# n2k-breakout-4_0-ISO.net
KiCad netlist of a schematic drawn in EAGLE
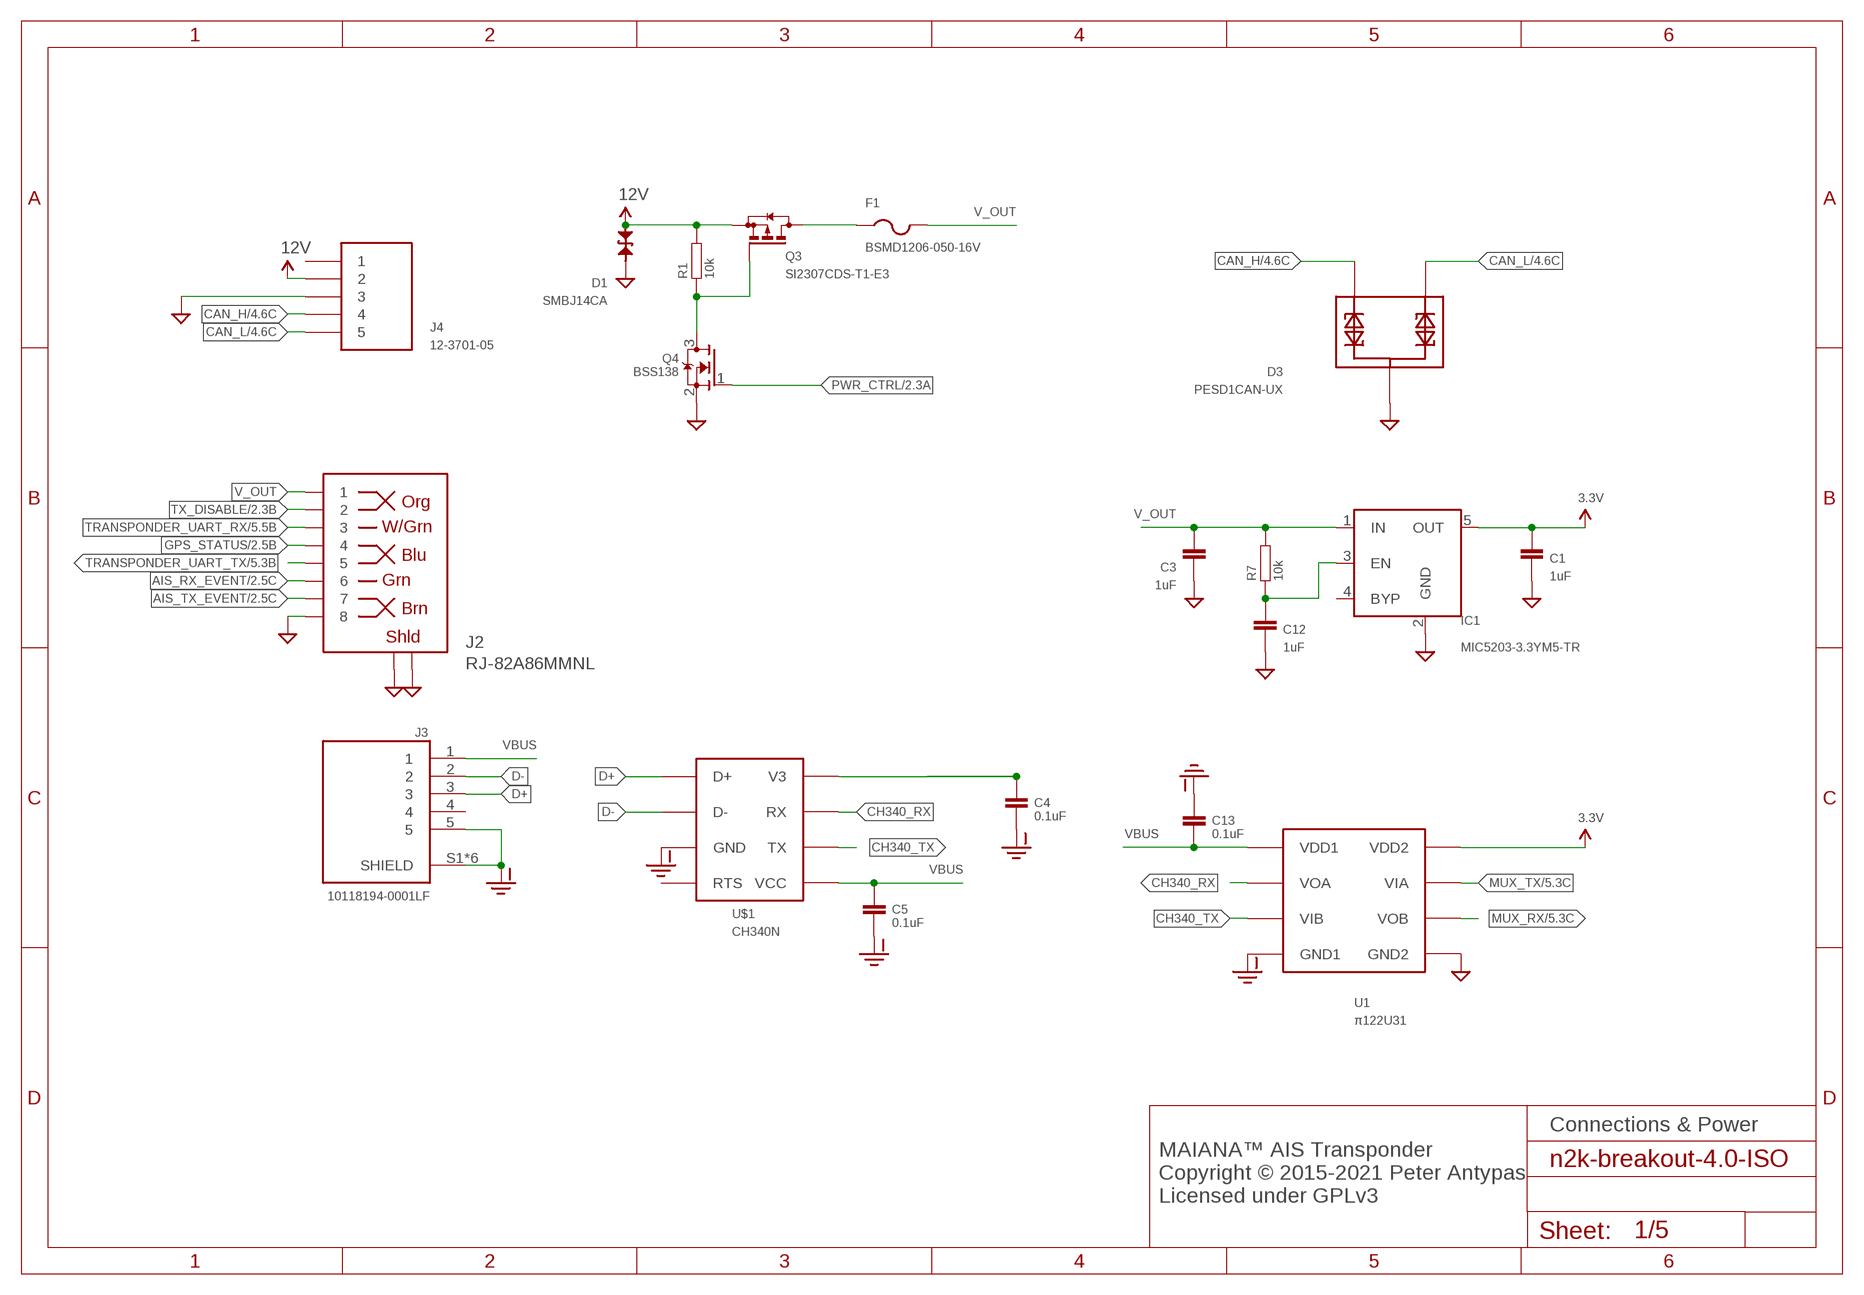
[diagram p0: schematic, sheet 1]
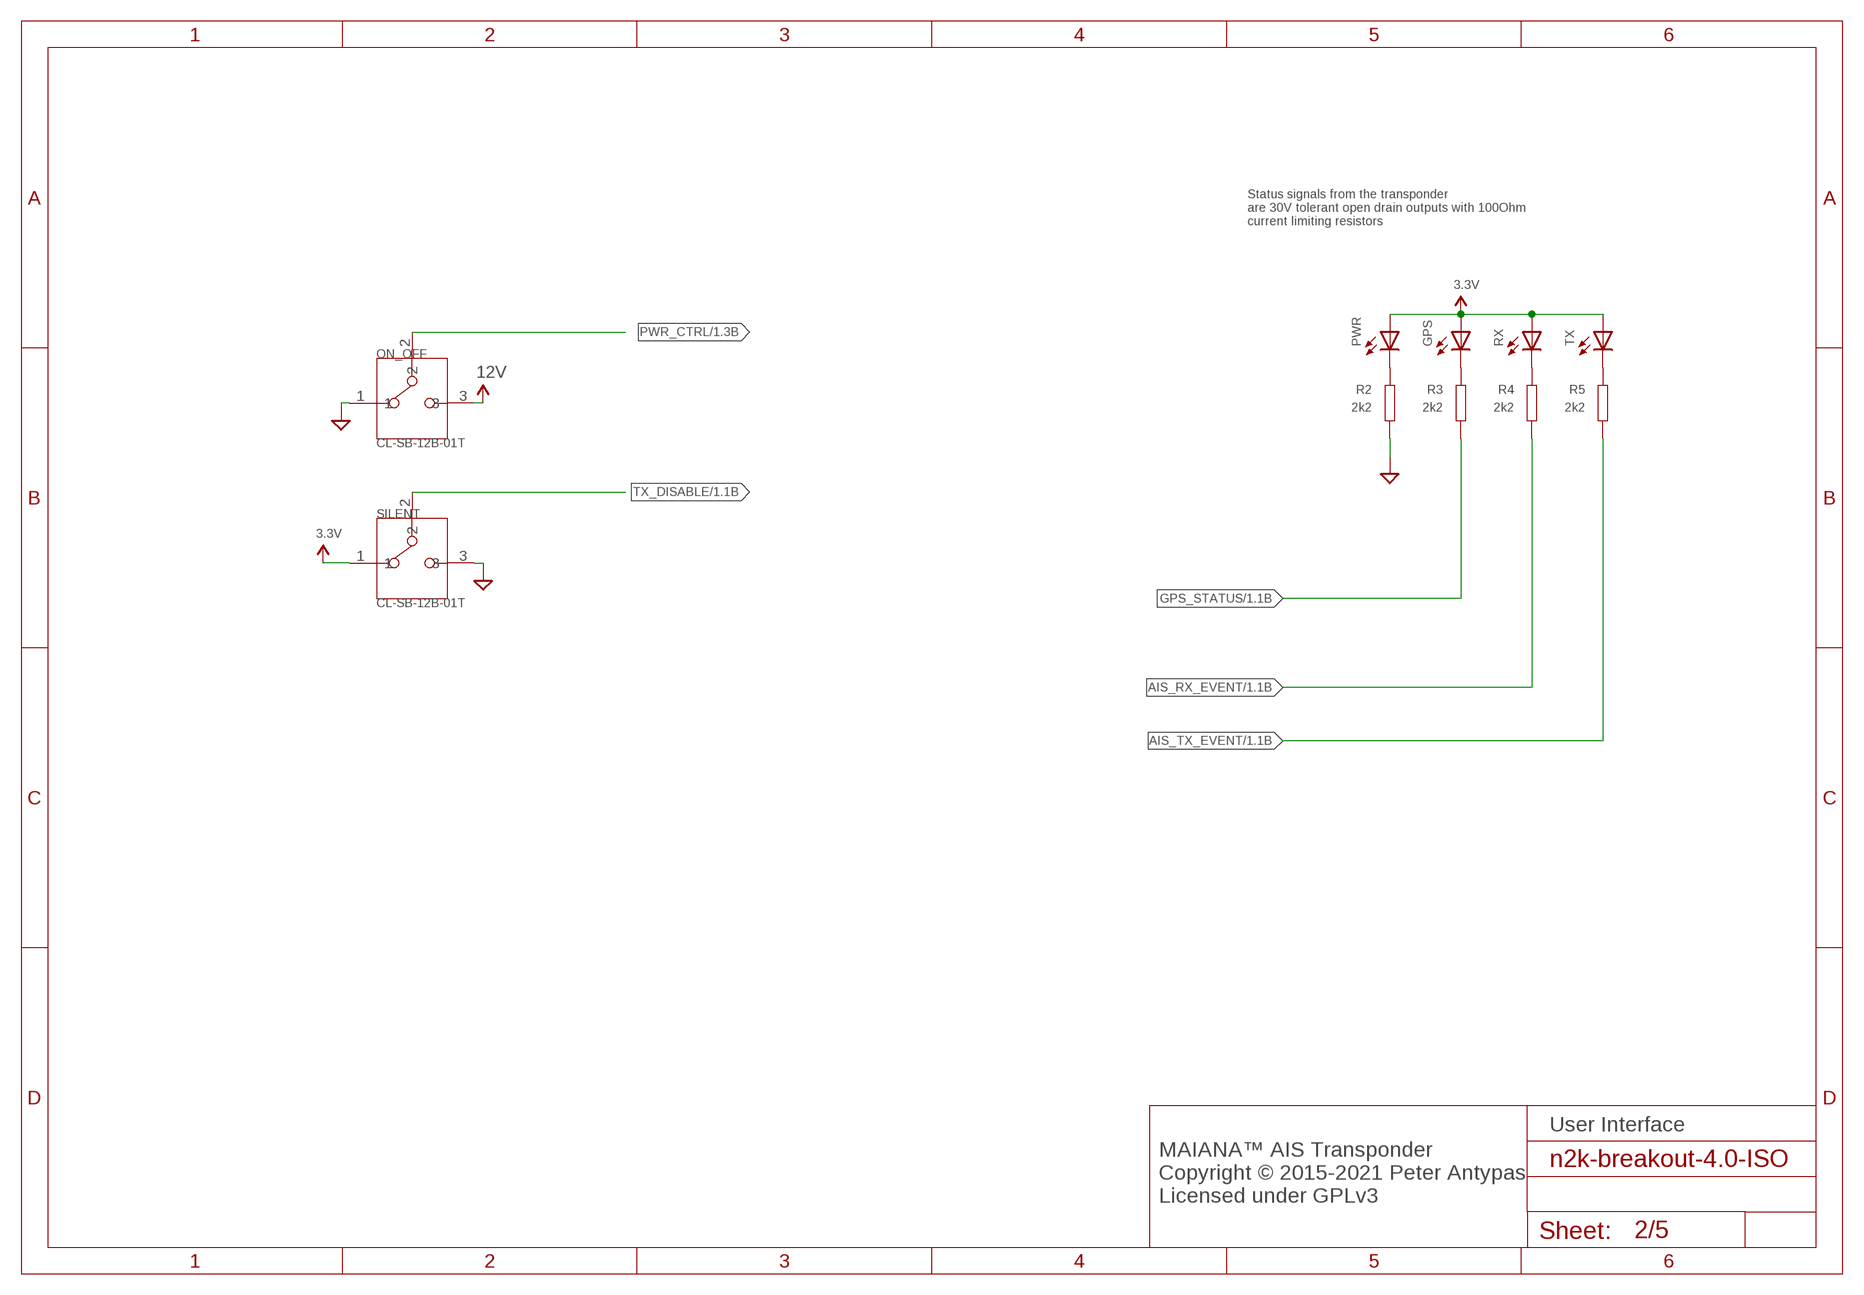
[diagram p1: schematic, sheet 2]
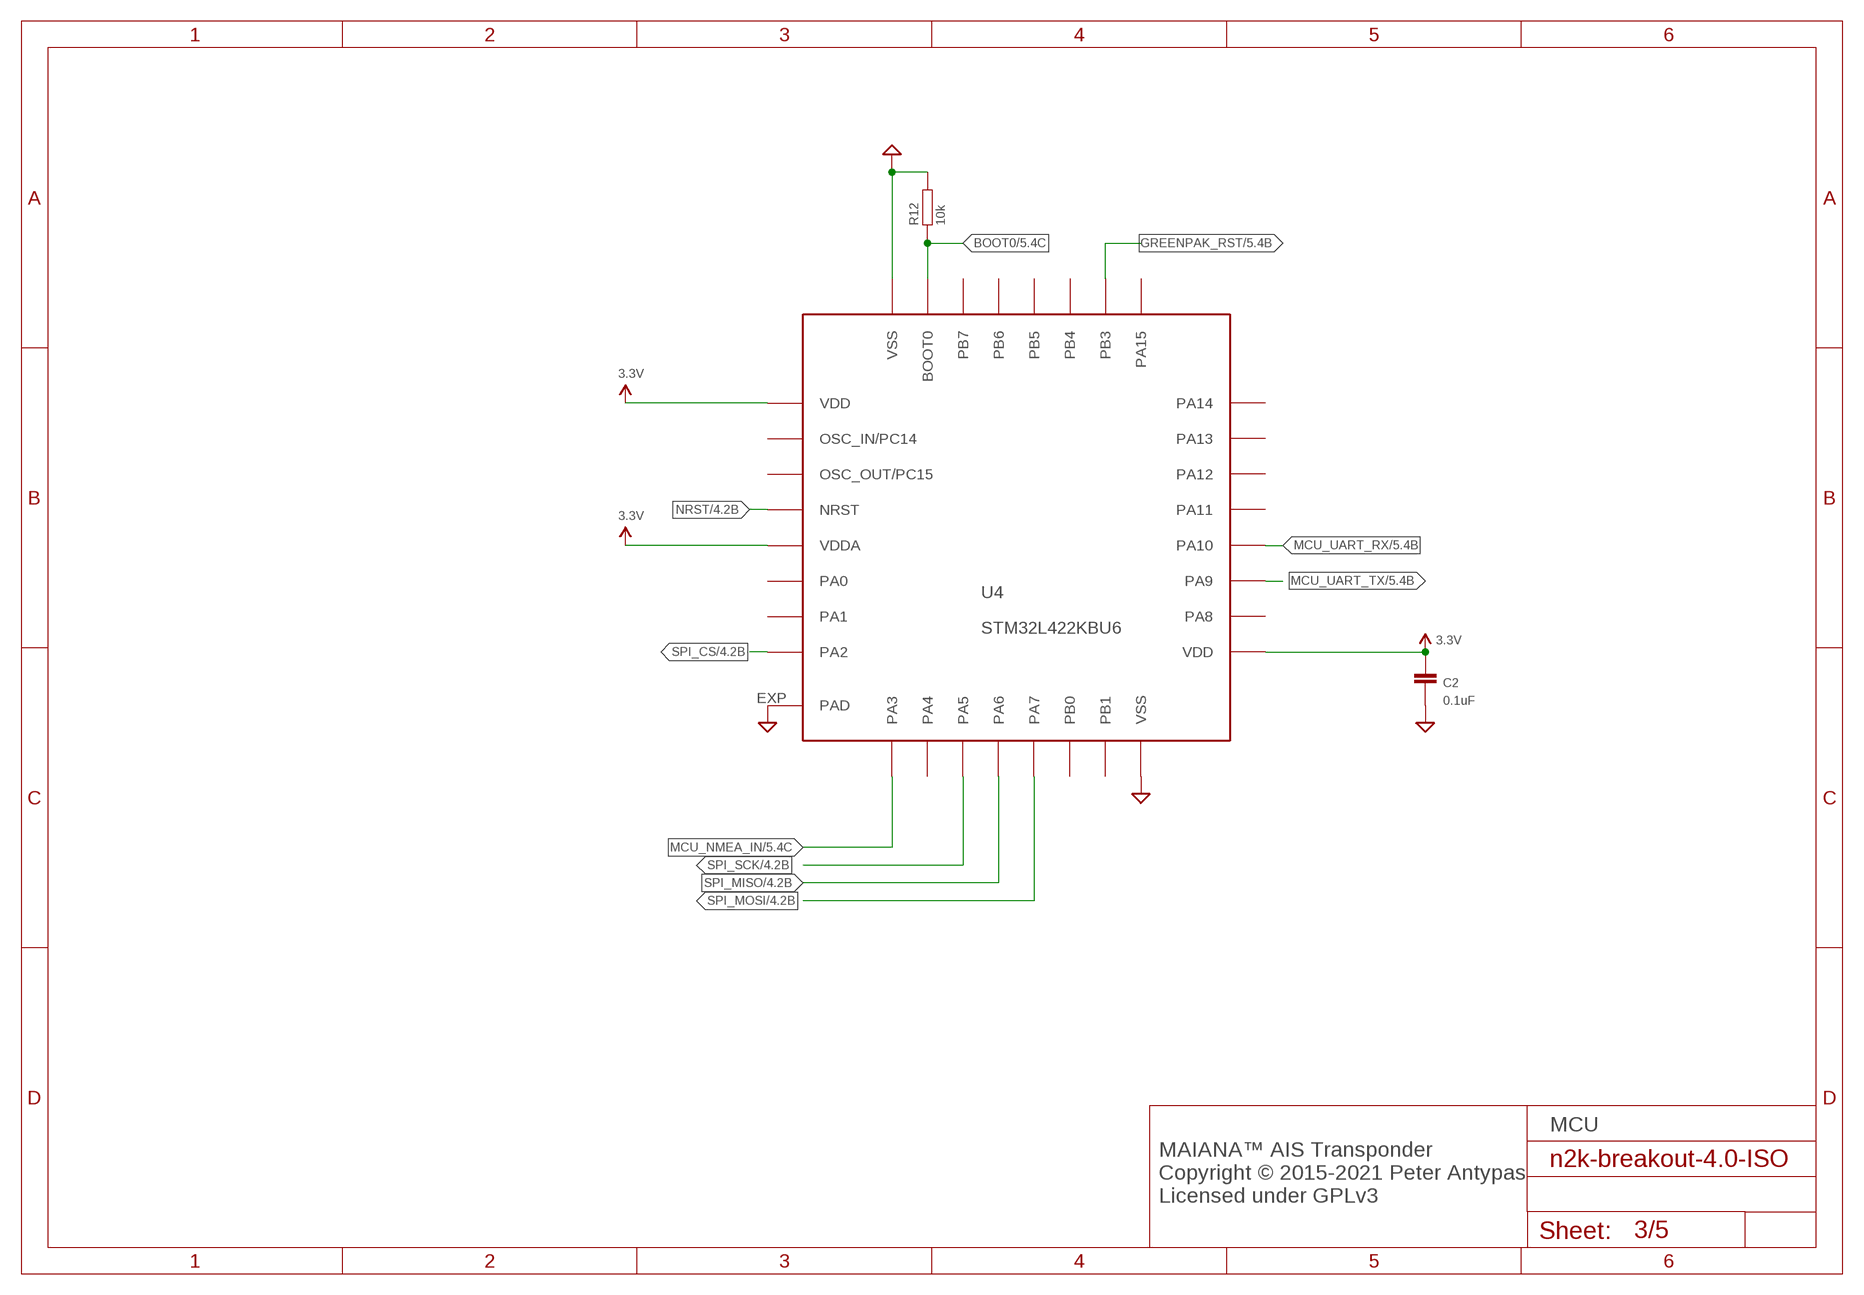
[diagram p2: schematic, sheet 3]
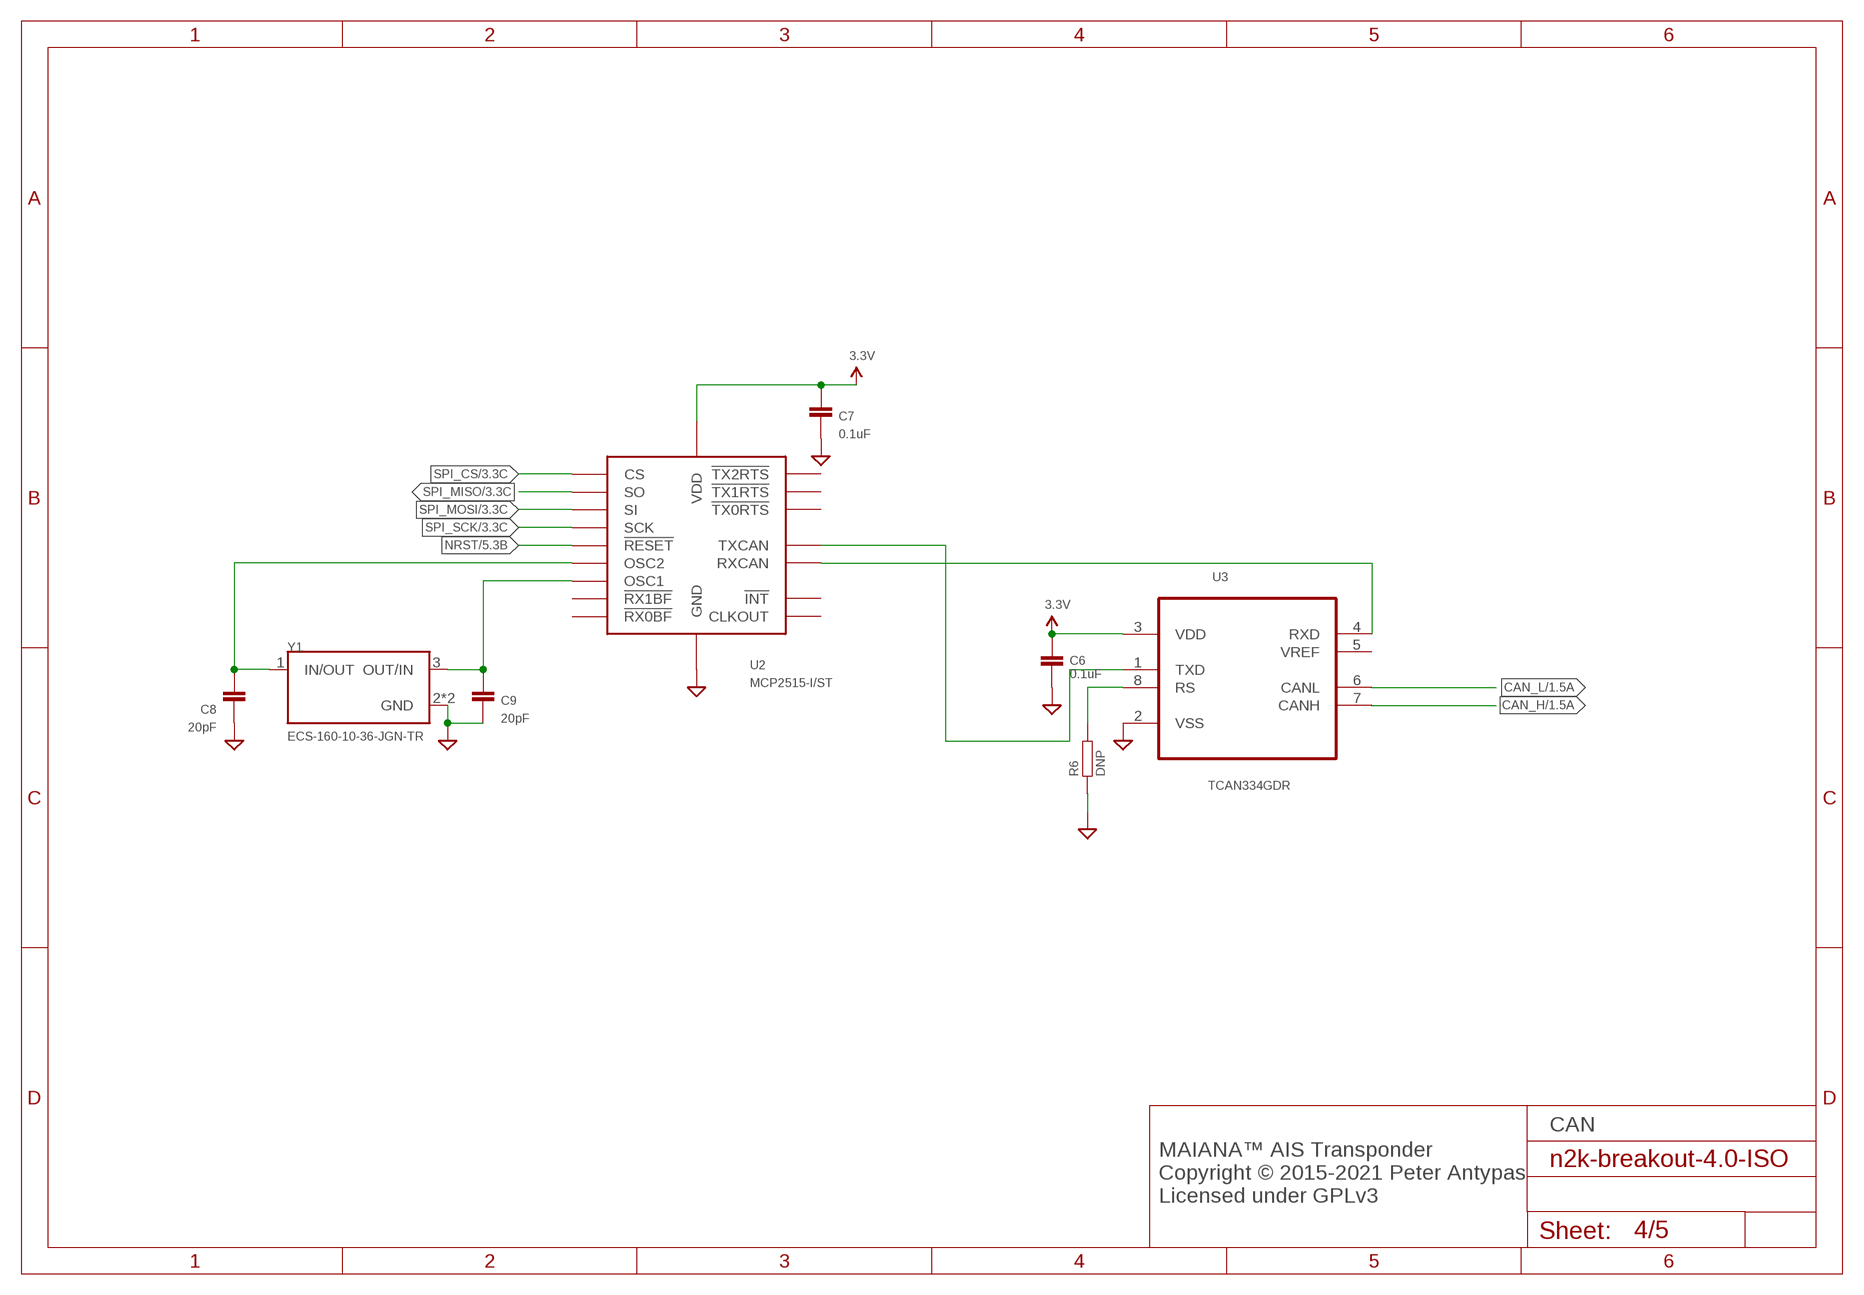
[diagram p3: schematic, sheet 4]
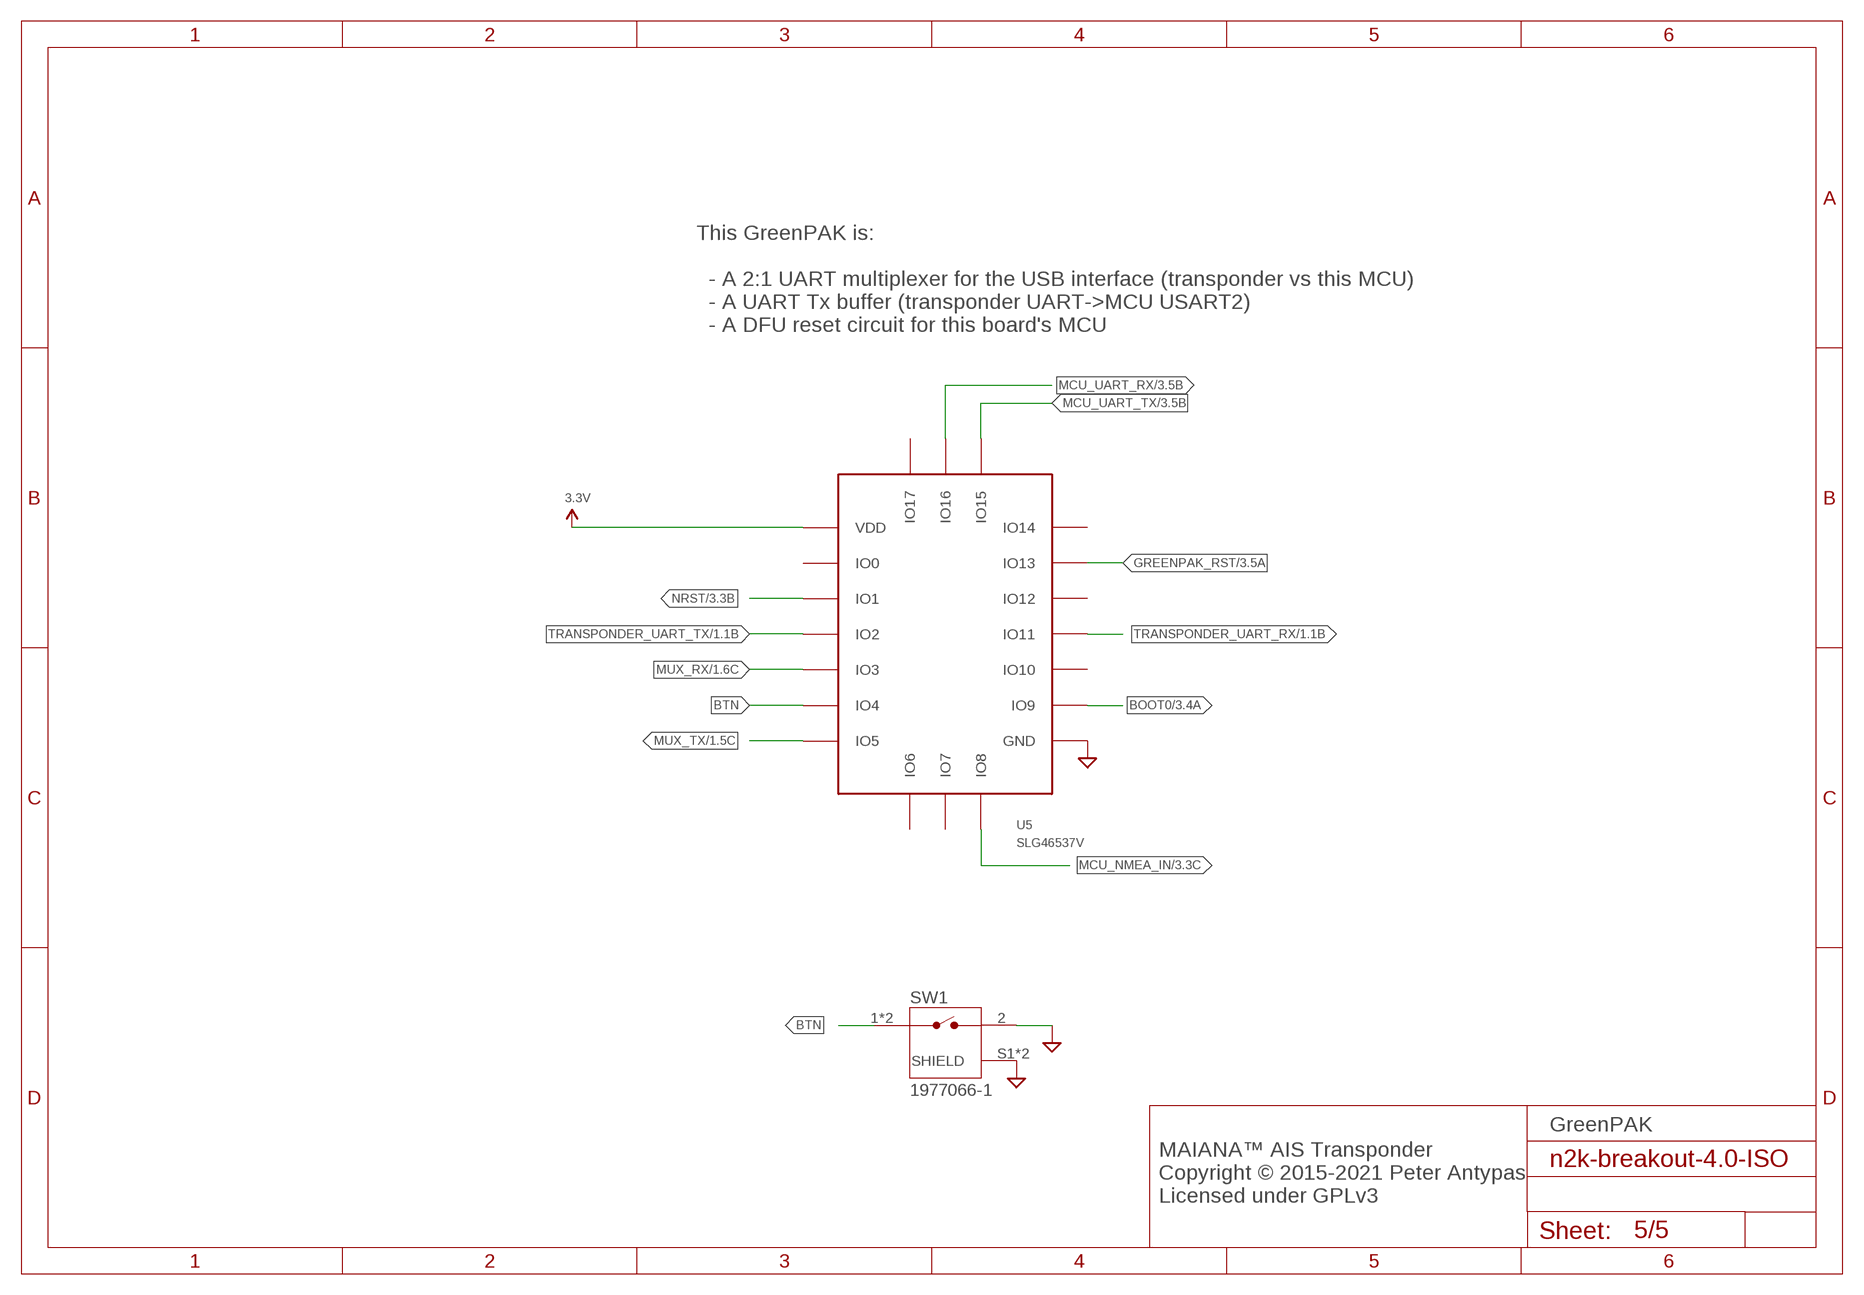
[diagram p4: schematic, sheet 5]

(export (version "E")
  (design (tool "Eeschema 10.0.6"))
  (components
    (comp (ref "GPS")
      (value "LEDCHIPLED_1206")
      (footprint "eagle-import:CHIPLED_1206")
      (fields (field (name "PARTNO") "TJ-S3216CL9T5ALC2G-A5"))
      (libsource (lib "eagle-import") (part "LEDCHIPLED_1206"))
    )
    (comp (ref "ON_OFF")
      (value "CL-SB-12B-01T")
      (footprint "eagle-import:CL-SB-12B")
      (fields (field (name "MF") "Nidec Copal"))
      (libsource (lib "eagle-import") (part "CL-SB-12B-01T"))
    )
    (comp (ref "PWR")
      (value "LEDCHIPLED_1206")
      (footprint "eagle-import:CHIPLED_1206")
      (fields (field (name "PARTNO") "TJ-S3216CL9T5ALC2G-A5"))
      (libsource (lib "eagle-import") (part "LEDCHIPLED_1206"))
    )
    (comp (ref "R2")
      (value "2k2")
      (footprint "eagle-import:0603")
      (fields (field (name "PARTNO") "CR0603-FX-2201ELF "))
      (libsource (lib "eagle-import") (part "RESISTOR0603"))
    )
    (comp (ref "R3")
      (value "2k2")
      (footprint "eagle-import:0603")
      (fields (field (name "PARTNO") "CR0603-FX-2201ELF"))
      (libsource (lib "eagle-import") (part "RESISTOR0603"))
    )
    (comp (ref "R4")
      (value "2k2")
      (footprint "eagle-import:0603")
      (fields (field (name "PARTNO") "CR0603-FX-2201ELF "))
      (libsource (lib "eagle-import") (part "RESISTOR0603"))
    )
    (comp (ref "R5")
      (value "2k2")
      (footprint "eagle-import:0603")
      (fields (field (name "PARTNO") "CR0603-FX-2201ELF "))
      (libsource (lib "eagle-import") (part "RESISTOR0603"))
    )
    (comp (ref "RX")
      (value "LEDCHIPLED_1206")
      (footprint "eagle-import:CHIPLED_1206")
      (fields (field (name "PARTNO") "TJ-S3216CL9T5ALC2G-A5"))
      (libsource (lib "eagle-import") (part "LEDCHIPLED_1206"))
    )
    (comp (ref "SILENT")
      (value "CL-SB-12B-01T")
      (footprint "eagle-import:CL-SB-12B")
      (fields (field (name "MF") "Nidec Copal"))
      (libsource (lib "eagle-import") (part "CL-SB-12B-01T"))
    )
    (comp (ref "TX")
      (value "LEDCHIPLED_1206")
      (footprint "eagle-import:CHIPLED_1206")
      (fields (field (name "PARTNO") "TJ-S3216CL9T5ALC2G-A5"))
      (libsource (lib "eagle-import") (part "LEDCHIPLED_1206"))
    )
    (comp (ref "C1")
      (value "1uF")
      (footprint "eagle-import:0603")
      (fields (field (name "PARTNO") "CC0603KRX5R8BB105 "))
      (libsource (lib "eagle-import") (part "CAPACITOR0603"))
    )
    (comp (ref "C3")
      (value "1uF")
      (footprint "eagle-import:0603")
      (fields (field (name "PARTNO") "CC0603KRX5R8BB105 "))
      (libsource (lib "eagle-import") (part "CAPACITOR0603"))
    )
    (comp (ref "C4")
      (value "0.1uF")
      (footprint "eagle-import:0603")
      (fields (field (name "PARTNO") "06035C104KAT2A "))
      (libsource (lib "eagle-import") (part "CAPACITOR0603"))
    )
    (comp (ref "C5")
      (value "0.1uF")
      (footprint "eagle-import:0603")
      (fields (field (name "PARTNO") "06035C104KAT2A "))
      (libsource (lib "eagle-import") (part "CAPACITOR0603"))
    )
    (comp (ref "C12")
      (value "1uF")
      (footprint "eagle-import:0603")
      (fields (field (name "PARTNO") "CC0603KRX5R8BB105 "))
      (libsource (lib "eagle-import") (part "CAPACITOR0603"))
    )
    (comp (ref "C13")
      (value "0.1uF")
      (footprint "eagle-import:0603")
      (fields (field (name "PARTNO") "06035C104KAT2A "))
      (libsource (lib "eagle-import") (part "CAPACITOR0603"))
    )
    (comp (ref "D1")
      (value "SMBJ14CA")
      (footprint "eagle-import:SMB-BIDIR")
      (fields (field (name "PARTNO") "SMBJ14CA "))
      (libsource (lib "eagle-import") (part "DIODE-TVS-BIDIRSMB"))
    )
    (comp (ref "D3")
      (value "PESD1CAN-UX")
      (footprint "eagle-import:SOT65P210X110-3N")
      (libsource (lib "eagle-import") (part "PESD1CAN-UX"))
    )
    (comp (ref "F1")
      (value "BSMD1206-050-16V")
      (footprint "eagle-import:R1206")
      (fields (field (name "PARTNO") "BSMD1206-050-16V "))
      (libsource (lib "eagle-import") (part "PTCFUSE-1206"))
    )
    (comp (ref "IC1")
      (value "MIC5203-3.3YM5-TR")
      (footprint "eagle-import:SOT23-5")
      (libsource (lib "eagle-import") (part "MIC5219XX"))
    )
    (comp (ref "J2")
      (value "RJ-82A86MMNL")
      (footprint "eagle-import:RJ-82A86MMNL")
      (libsource (lib "eagle-import") (part "RJ-82A86MMNL"))
    )
    (comp (ref "J3")
      (value "10118194-0001LF")
      (footprint "eagle-import:AMPHENOL_10118194-0001LF")
      (fields (field (name "MF") "Amphenol ICC (FCI)"))
      (libsource (lib "eagle-import") (part "10118194-0001LF"))
    )
    (comp (ref "J4")
      (value "12-3701-05")
      (footprint "eagle-import:MICRO_C_5PIN")
      (libsource (lib "eagle-import") (part "12-3701-05"))
    )
    (comp (ref "Q3")
      (value "SI2307CDS-T1-E3")
      (footprint "eagle-import:SOT23")
      (fields (field (name "PARTNO") "SI2307CDS-T1-E3 "))
      (libsource (lib "eagle-import") (part "BSS84"))
    )
    (comp (ref "Q4")
      (value "BSS138")
      (footprint "eagle-import:SOT23")
      (libsource (lib "eagle-import") (part "MOSFET-NREFLOW"))
    )
    (comp (ref "R1")
      (value "10k")
      (footprint "eagle-import:0603")
      (fields (field (name "PARTNO") "RC0603FR-0710KL"))
      (libsource (lib "eagle-import") (part "RESISTOR0603"))
    )
    (comp (ref "R7")
      (value "10k")
      (footprint "eagle-import:0603")
      (fields (field (name "PARTNO") "RC0603FR-0710KL"))
      (libsource (lib "eagle-import") (part "RESISTOR0603"))
    )
    (comp (ref "U$1")
      (value "CH340N")
      (footprint "eagle-import:SOIC-8")
      (libsource (lib "eagle-import") (part "CH330N"))
    )
    (comp (ref "U1")
      (value "π122U31")
      (footprint "eagle-import:SOIC8")
      (libsource (lib "eagle-import") (part "PI122U3X"))
    )
    (comp (ref "C6")
      (value "0.1uF")
      (footprint "eagle-import:0603")
      (fields (field (name "PARTNO") "06035C104KAT2A "))
      (libsource (lib "eagle-import") (part "CAPACITOR0603"))
    )
    (comp (ref "C7")
      (value "0.1uF")
      (footprint "eagle-import:0603")
      (fields (field (name "PARTNO") "06035C104KAT2A "))
      (libsource (lib "eagle-import") (part "CAPACITOR0603"))
    )
    (comp (ref "C8")
      (value "20pF")
      (footprint "eagle-import:0603")
      (fields (field (name "PARTNO") "GRM1885C1H200JA01D "))
      (libsource (lib "eagle-import") (part "CAPACITOR0603"))
    )
    (comp (ref "C9")
      (value "20pF")
      (footprint "eagle-import:0603")
      (fields (field (name "PARTNO") "GRM1885C1H200JA01D "))
      (libsource (lib "eagle-import") (part "CAPACITOR0603"))
    )
    (comp (ref "R6")
      (value "DNP")
      (footprint "eagle-import:0603")
      (fields (field (name "PARTNO") "RC0603FR-0710KL"))
      (libsource (lib "eagle-import") (part "RESISTOR0603"))
    )
    (comp (ref "U2")
      (value "MCP2515-I/ST")
      (footprint "eagle-import:TSSOP20")
      (libsource (lib "eagle-import") (part "MCP2515TSSOP20"))
    )
    (comp (ref "U3")
      (value "TCAN334GDR")
      (footprint "eagle-import:SOIC127P600X175-8N")
      (fields (field (name "MF") "Microchip") (field (name "MP") "MCP2551T-I/SN"))
      (libsource (lib "eagle-import") (part "MCP2551T-I/SN"))
    )
    (comp (ref "Y1")
      (value "ECS-160-10-36-JGN-TR")
      (footprint "eagle-import:XTAL_ECS-160-10-36-JGN-TR")
      (fields (field (name "MF") "ECS Inc.") (field (name "MP") "ECS-300-8-36CKM-TR"))
      (libsource (lib "eagle-import") (part "ECS-300-8-36CKM-TR"))
    )
    (comp (ref "SW1")
      (value "1977066-1")
      (footprint "eagle-import:TE_1977066-1")
      (fields (field (name "MF") "TE Connectivity"))
      (libsource (lib "eagle-import") (part "1977066-1"))
    )
    (comp (ref "U5")
      (value "SLG46537V")
      (footprint "eagle-import:STQFN20L")
      (libsource (lib "eagle-import") (part "SLG46537"))
    )
    (comp (ref "C2")
      (value "0.1uF")
      (footprint "eagle-import:0603")
      (fields (field (name "PARTNO") "06035C104KAT2A "))
      (libsource (lib "eagle-import") (part "CAPACITOR0603"))
    )
    (comp (ref "R12")
      (value "10k")
      (footprint "eagle-import:0603")
      (fields (field (name "PARTNO") "RC0603FR-0710KL"))
      (libsource (lib "eagle-import") (part "RESISTOR0603"))
    )
    (comp (ref "U4")
      (value "STM32L422KBU6")
      (footprint "eagle-import:QFN32")
      (libsource (lib "eagle-import") (part "STM32L432KXXX"))
    )
  )
  (nets
    (net (code "1") (name "3.3V") (class "Default")
      (node (ref "C1") (pin "P$1") (pinfunction "1_P$1") (pintype "passive"))
      (node (ref "C2") (pin "P$1") (pinfunction "1_P$1") (pintype "passive"))
      (node (ref "C6") (pin "P$1") (pinfunction "1_P$1") (pintype "passive"))
      (node (ref "C7") (pin "P$1") (pinfunction "1_P$1") (pintype "passive"))
      (node (ref "GPS") (pin "A") (pinfunction "A_A") (pintype "passive"))
      (node (ref "IC1") (pin "5") (pinfunction "OUT_5") (pintype "output"))
      (node (ref "PWR") (pin "A") (pinfunction "A_A") (pintype "passive"))
      (node (ref "RX") (pin "A") (pinfunction "A_A") (pintype "passive"))
      (node (ref "SILENT") (pin "1") (pinfunction "1_1") (pintype "bidirectional"))
      (node (ref "TX") (pin "A") (pinfunction "A_A") (pintype "passive"))
      (node (ref "U1") (pin "8") (pinfunction "VDD2_8") (pintype "bidirectional"))
      (node (ref "U2") (pin "20") (pinfunction "VDD_20") (pintype "bidirectional"))
      (node (ref "U3") (pin "3") (pinfunction "VDD_3") (pintype "power_in"))
      (node (ref "U4") (pin "1") (pinfunction "VDD_1") (pintype "bidirectional"))
      (node (ref "U4") (pin "17") (pinfunction "VDD_17") (pintype "bidirectional"))
      (node (ref "U4") (pin "5") (pinfunction "VDDA_5") (pintype "bidirectional"))
      (node (ref "U5") (pin "P$1") (pinfunction "VDD_P$1") (pintype "bidirectional"))
    )
    (net (code "2") (name "12V") (class "Default")
      (node (ref "D1") (pin "A") (pinfunction "P$1_A") (pintype "bidirectional"))
      (node (ref "J4") (pin "2") (pinfunction "2_2") (pintype "bidirectional"))
      (node (ref "ON_OFF") (pin "3") (pinfunction "3_3") (pintype "bidirectional"))
      (node (ref "Q3") (pin "2") (pinfunction "S_2") (pintype "passive"))
      (node (ref "R1") (pin "P$2") (pinfunction "P$2_P$2") (pintype "passive"))
    )
    (net (code "3") (name "AIS_RX_EVENT") (class "Default")
      (node (ref "J2") (pin "P$6") (pinfunction "6_P$6") (pintype "bidirectional"))
      (node (ref "R4") (pin "P$2") (pinfunction "P$2_P$2") (pintype "passive"))
    )
    (net (code "4") (name "AIS_TX_EVENT") (class "Default")
      (node (ref "J2") (pin "P$7") (pinfunction "7_P$7") (pintype "bidirectional"))
      (node (ref "R5") (pin "P$2") (pinfunction "P$2_P$2") (pintype "passive"))
    )
    (net (code "5") (name "BOOT0") (class "Default")
      (node (ref "R12") (pin "P$1") (pinfunction "P$1_P$1") (pintype "passive"))
      (node (ref "U4") (pin "31") (pinfunction "BOOT0_31") (pintype "bidirectional"))
      (node (ref "U5") (pin "P$12") (pinfunction "IO9_P$12") (pintype "bidirectional"))
    )
    (net (code "6") (name "BTN") (class "Default")
      (node (ref "SW1") (pin "1") (pinfunction "1_1") (pintype "passive"))
      (node (ref "SW1") (pin "3") (pinfunction "1_3") (pintype "passive"))
      (node (ref "U5") (pin "P$6") (pinfunction "IO4_P$6") (pintype "bidirectional"))
    )
    (net (code "7") (name "CAN_H") (class "Default")
      (node (ref "D3") (pin "2") (pinfunction "P$2_2") (pintype "bidirectional"))
      (node (ref "J4") (pin "4") (pinfunction "4_4") (pintype "bidirectional"))
      (node (ref "U3") (pin "7") (pinfunction "CANH_7") (pintype "bidirectional"))
    )
    (net (code "8") (name "CAN_L") (class "Default")
      (node (ref "D3") (pin "1") (pinfunction "P$1_1") (pintype "bidirectional"))
      (node (ref "J4") (pin "5") (pinfunction "5_5") (pintype "bidirectional"))
      (node (ref "U3") (pin "6") (pinfunction "CANL_6") (pintype "bidirectional"))
    )
    (net (code "9") (name "CH340_RX") (class "Default")
      (node (ref "U$1") (pin "7") (pinfunction "RX_7") (pintype "bidirectional"))
      (node (ref "U1") (pin "2") (pinfunction "VOA_2") (pintype "bidirectional"))
    )
    (net (code "10") (name "CH340_TX") (class "Default")
      (node (ref "U$1") (pin "6") (pinfunction "TX_6") (pintype "bidirectional"))
      (node (ref "U1") (pin "3") (pinfunction "VIB_3") (pintype "bidirectional"))
    )
    (net (code "11") (name "D+") (class "Default")
      (node (ref "J3") (pin "3") (pinfunction "3_3") (pintype "passive"))
      (node (ref "U$1") (pin "1") (pinfunction "D+_1") (pintype "bidirectional"))
    )
    (net (code "12") (name "D-") (class "Default")
      (node (ref "J3") (pin "2") (pinfunction "2_2") (pintype "passive"))
      (node (ref "U$1") (pin "2") (pinfunction "D-_2") (pintype "bidirectional"))
    )
    (net (code "13") (name "GND") (class "Default")
      (node (ref "C1") (pin "P$2") (pinfunction "2_P$2") (pintype "passive"))
      (node (ref "C12") (pin "P$2") (pinfunction "2_P$2") (pintype "passive"))
      (node (ref "C2") (pin "P$2") (pinfunction "2_P$2") (pintype "passive"))
      (node (ref "C3") (pin "P$2") (pinfunction "2_P$2") (pintype "passive"))
      (node (ref "C6") (pin "P$2") (pinfunction "2_P$2") (pintype "passive"))
      (node (ref "C7") (pin "P$2") (pinfunction "2_P$2") (pintype "passive"))
      (node (ref "C8") (pin "P$2") (pinfunction "2_P$2") (pintype "passive"))
      (node (ref "C9") (pin "P$2") (pinfunction "2_P$2") (pintype "passive"))
      (node (ref "D1") (pin "C") (pinfunction "P$2_C") (pintype "bidirectional"))
      (node (ref "D3") (pin "3") (pinfunction "P$3_3") (pintype "bidirectional"))
      (node (ref "IC1") (pin "2") (pinfunction "GND_2") (pintype "power_in"))
      (node (ref "J2") (pin "P$10") (pinfunction "SHLD_P$10") (pintype "bidirectional"))
      (node (ref "J2") (pin "P$11") (pinfunction "SHLD_P$11") (pintype "bidirectional"))
      (node (ref "J2") (pin "P$12") (pinfunction "SHLD_P$12") (pintype "bidirectional"))
      (node (ref "J2") (pin "P$8") (pinfunction "8_P$8") (pintype "bidirectional"))
      (node (ref "J2") (pin "P$9") (pinfunction "SHLD_P$9") (pintype "bidirectional"))
      (node (ref "J4") (pin "3") (pinfunction "3_3") (pintype "bidirectional"))
      (node (ref "ON_OFF") (pin "1") (pinfunction "1_1") (pintype "bidirectional"))
      (node (ref "Q4") (pin "2") (pinfunction "S_2") (pintype "bidirectional"))
      (node (ref "R12") (pin "P$2") (pinfunction "P$2_P$2") (pintype "passive"))
      (node (ref "R2") (pin "P$2") (pinfunction "P$2_P$2") (pintype "passive"))
      (node (ref "R6") (pin "P$1") (pinfunction "P$1_P$1") (pintype "passive"))
      (node (ref "SILENT") (pin "3") (pinfunction "3_3") (pintype "bidirectional"))
      (node (ref "SW1") (pin "2") (pinfunction "2_2") (pintype "passive"))
      (node (ref "SW1") (pin "S1") (pinfunction "SHIELD_S1") (pintype "passive"))
      (node (ref "SW1") (pin "S2") (pinfunction "SHIELD_S2") (pintype "passive"))
      (node (ref "U1") (pin "5") (pinfunction "GND2_5") (pintype "bidirectional"))
      (node (ref "U2") (pin "10") (pinfunction "GND_10") (pintype "bidirectional"))
      (node (ref "U3") (pin "2") (pinfunction "VSS_2") (pintype "passive"))
      (node (ref "U4") (pin "16") (pinfunction "VSS_16") (pintype "bidirectional"))
      (node (ref "U4") (pin "32") (pinfunction "VSS_32") (pintype "bidirectional"))
      (node (ref "U4") (pin "EXP") (pinfunction "PAD_EXP") (pintype "bidirectional"))
      (node (ref "U5") (pin "P$11") (pinfunction "GND_P$11") (pintype "bidirectional"))
      (node (ref "Y1") (pin "2") (pinfunction "GND_2") (pintype "power_in"))
      (node (ref "Y1") (pin "4") (pinfunction "GND_4") (pintype "power_in"))
    )
    (net (code "14") (name "GND-ISO") (class "Default")
      (node (ref "C13") (pin "P$1") (pinfunction "1_P$1") (pintype "passive"))
      (node (ref "C4") (pin "P$2") (pinfunction "2_P$2") (pintype "passive"))
      (node (ref "C5") (pin "P$2") (pinfunction "2_P$2") (pintype "passive"))
      (node (ref "J3") (pin "5") (pinfunction "5_5") (pintype "passive"))
      (node (ref "J3") (pin "S1") (pinfunction "SHIELD_S1") (pintype "passive"))
      (node (ref "J3") (pin "S2") (pinfunction "SHIELD_S2") (pintype "passive"))
      (node (ref "J3") (pin "S3") (pinfunction "SHIELD_S3") (pintype "passive"))
      (node (ref "J3") (pin "S4") (pinfunction "SHIELD_S4") (pintype "passive"))
      (node (ref "J3") (pin "S5") (pinfunction "SHIELD_S5") (pintype "passive"))
      (node (ref "J3") (pin "S6") (pinfunction "SHIELD_S6") (pintype "passive"))
      (node (ref "U$1") (pin "3") (pinfunction "GND_3") (pintype "bidirectional"))
      (node (ref "U1") (pin "4") (pinfunction "GND1_4") (pintype "bidirectional"))
    )
    (net (code "15") (name "GPS_STATUS") (class "Default")
      (node (ref "J2") (pin "P$4") (pinfunction "4_P$4") (pintype "bidirectional"))
      (node (ref "R3") (pin "P$2") (pinfunction "P$2_P$2") (pintype "passive"))
    )
    (net (code "16") (name "GREENPAK_RST") (class "Default")
      (node (ref "U4") (pin "26") (pinfunction "PB3_26") (pintype "bidirectional"))
      (node (ref "U5") (pin "P$16") (pinfunction "IO13_P$16") (pintype "bidirectional"))
    )
    (net (code "17") (name "MCU_NMEA_IN") (class "Default")
      (node (ref "U4") (pin "9") (pinfunction "PA3_9") (pintype "bidirectional"))
      (node (ref "U5") (pin "P$10") (pinfunction "IO8_P$10") (pintype "bidirectional"))
    )
    (net (code "18") (name "MCU_UART_RX") (class "Default")
      (node (ref "U4") (pin "20") (pinfunction "PA10_20") (pintype "bidirectional"))
      (node (ref "U5") (pin "P$19") (pinfunction "IO16_P$19") (pintype "bidirectional"))
    )
    (net (code "19") (name "MCU_UART_TX") (class "Default")
      (node (ref "U4") (pin "19") (pinfunction "PA9_19") (pintype "bidirectional"))
      (node (ref "U5") (pin "P$18") (pinfunction "IO15_P$18") (pintype "bidirectional"))
    )
    (net (code "20") (name "MUX_RX") (class "Default")
      (node (ref "U1") (pin "6") (pinfunction "VOB_6") (pintype "bidirectional"))
      (node (ref "U5") (pin "P$5") (pinfunction "IO3_P$5") (pintype "bidirectional"))
    )
    (net (code "21") (name "MUX_TX") (class "Default")
      (node (ref "U1") (pin "7") (pinfunction "VIA_7") (pintype "bidirectional"))
      (node (ref "U5") (pin "P$7") (pinfunction "IO5_P$7") (pintype "bidirectional"))
    )
    (net (code "22") (name "NRST") (class "Default")
      (node (ref "U2") (pin "19") (pinfunction "~{RESET}_19") (pintype "bidirectional"))
      (node (ref "U4") (pin "4") (pinfunction "NRST_4") (pintype "bidirectional"))
      (node (ref "U5") (pin "P$3") (pinfunction "IO1_P$3") (pintype "bidirectional"))
    )
    (net (code "23") (name "Net-(C4-1)") (class "Default")
      (node (ref "C4") (pin "P$1") (pinfunction "1_P$1") (pintype "passive"))
      (node (ref "U$1") (pin "8") (pinfunction "V3_8") (pintype "bidirectional"))
    )
    (net (code "24") (name "Net-(C8-1)") (class "Default")
      (node (ref "C8") (pin "P$1") (pinfunction "1_P$1") (pintype "passive"))
      (node (ref "U2") (pin "8") (pinfunction "OSC2_8") (pintype "bidirectional"))
      (node (ref "Y1") (pin "1") (pinfunction "IN/OUT_1") (pintype "bidirectional"))
    )
    (net (code "25") (name "Net-(C9-1)") (class "Default")
      (node (ref "C9") (pin "P$1") (pinfunction "1_P$1") (pintype "passive"))
      (node (ref "U2") (pin "9") (pinfunction "OSC1_9") (pintype "bidirectional"))
      (node (ref "Y1") (pin "3") (pinfunction "OUT/IN_3") (pintype "bidirectional"))
    )
    (net (code "26") (name "Net-(C12-1)") (class "Default")
      (node (ref "C12") (pin "P$1") (pinfunction "1_P$1") (pintype "passive"))
      (node (ref "IC1") (pin "3") (pinfunction "EN_3") (pintype "input"))
      (node (ref "R7") (pin "P$1") (pinfunction "P$1_P$1") (pintype "passive"))
    )
    (net (code "27") (name "Net-(GPS-PadC)") (class "Default")
      (node (ref "GPS") (pin "C") (pinfunction "C_C") (pintype "passive"))
      (node (ref "R3") (pin "P$1") (pinfunction "P$1_P$1") (pintype "passive"))
    )
    (net (code "28") (name "Net-(PWR-PadC)") (class "Default")
      (node (ref "PWR") (pin "C") (pinfunction "C_C") (pintype "passive"))
      (node (ref "R2") (pin "P$1") (pinfunction "P$1_P$1") (pintype "passive"))
    )
    (net (code "29") (name "Net-(Q3-D)") (class "Default")
      (node (ref "F1") (pin "1") (pinfunction "1_1") (pintype "passive"))
      (node (ref "Q3") (pin "3") (pinfunction "D_3") (pintype "passive"))
    )
    (net (code "30") (name "Net-(Q3-G)") (class "Default")
      (node (ref "Q3") (pin "1") (pinfunction "G_1") (pintype "passive"))
      (node (ref "Q4") (pin "3") (pinfunction "D_3") (pintype "bidirectional"))
      (node (ref "R1") (pin "P$1") (pinfunction "P$1_P$1") (pintype "passive"))
    )
    (net (code "31") (name "Net-(R4-PadP$1)") (class "Default")
      (node (ref "R4") (pin "P$1") (pinfunction "P$1_P$1") (pintype "passive"))
      (node (ref "RX") (pin "C") (pinfunction "C_C") (pintype "passive"))
    )
    (net (code "32") (name "Net-(R5-PadP$1)") (class "Default")
      (node (ref "R5") (pin "P$1") (pinfunction "P$1_P$1") (pintype "passive"))
      (node (ref "TX") (pin "C") (pinfunction "C_C") (pintype "passive"))
    )
    (net (code "33") (name "Net-(U2-RXCAN)") (class "Default")
      (node (ref "U2") (pin "2") (pinfunction "RXCAN_2") (pintype "bidirectional"))
      (node (ref "U3") (pin "4") (pinfunction "RXD_4") (pintype "output"))
    )
    (net (code "34") (name "Net-(U2-TXCAN)") (class "Default")
      (node (ref "U2") (pin "1") (pinfunction "TXCAN_1") (pintype "bidirectional"))
      (node (ref "U3") (pin "1") (pinfunction "TXD_1") (pintype "input"))
    )
    (net (code "35") (name "Net-(U3-RS)") (class "Default")
      (node (ref "R6") (pin "P$2") (pinfunction "P$2_P$2") (pintype "passive"))
      (node (ref "U3") (pin "8") (pinfunction "RS_8") (pintype "input"))
    )
    (net (code "36") (name "PWR_CTRL") (class "Default")
      (node (ref "ON_OFF") (pin "2") (pinfunction "2_2") (pintype "bidirectional"))
      (node (ref "Q4") (pin "1") (pinfunction "G_1") (pintype "bidirectional"))
    )
    (net (code "37") (name "SPI_CS") (class "Default")
      (node (ref "U2") (pin "18") (pinfunction "CS_18") (pintype "bidirectional"))
      (node (ref "U4") (pin "8") (pinfunction "PA2_8") (pintype "bidirectional"))
    )
    (net (code "38") (name "SPI_MISO") (class "Default")
      (node (ref "U2") (pin "17") (pinfunction "SO_17") (pintype "bidirectional"))
      (node (ref "U4") (pin "12") (pinfunction "PA6_12") (pintype "bidirectional"))
    )
    (net (code "39") (name "SPI_MOSI") (class "Default")
      (node (ref "U2") (pin "16") (pinfunction "SI_16") (pintype "bidirectional"))
      (node (ref "U4") (pin "13") (pinfunction "PA7_13") (pintype "bidirectional"))
    )
    (net (code "40") (name "SPI_SCK") (class "Default")
      (node (ref "U2") (pin "14") (pinfunction "SCK_14") (pintype "bidirectional"))
      (node (ref "U4") (pin "11") (pinfunction "PA5_11") (pintype "bidirectional"))
    )
    (net (code "41") (name "TRANSPONDER_UART_RX") (class "Default")
      (node (ref "J2") (pin "P$3") (pinfunction "3_P$3") (pintype "bidirectional"))
      (node (ref "U5") (pin "P$14") (pinfunction "IO11_P$14") (pintype "bidirectional"))
    )
    (net (code "42") (name "TRANSPONDER_UART_TX") (class "Default")
      (node (ref "J2") (pin "P$5") (pinfunction "5_P$5") (pintype "bidirectional"))
      (node (ref "U5") (pin "P$4") (pinfunction "IO2_P$4") (pintype "bidirectional"))
    )
    (net (code "43") (name "TX_DISABLE") (class "Default")
      (node (ref "J2") (pin "P$2") (pinfunction "2_P$2") (pintype "bidirectional"))
      (node (ref "SILENT") (pin "2") (pinfunction "2_2") (pintype "bidirectional"))
    )
    (net (code "44") (name "VBUS") (class "Default")
      (node (ref "C13") (pin "P$2") (pinfunction "2_P$2") (pintype "passive"))
      (node (ref "C5") (pin "P$1") (pinfunction "1_P$1") (pintype "passive"))
      (node (ref "J3") (pin "1") (pinfunction "1_1") (pintype "passive"))
      (node (ref "U$1") (pin "5") (pinfunction "VCC_5") (pintype "bidirectional"))
      (node (ref "U1") (pin "1") (pinfunction "VDD1_1") (pintype "bidirectional"))
    )
    (net (code "45") (name "V_OUT") (class "Default")
      (node (ref "C3") (pin "P$1") (pinfunction "1_P$1") (pintype "passive"))
      (node (ref "F1") (pin "2") (pinfunction "2_2") (pintype "passive"))
      (node (ref "IC1") (pin "1") (pinfunction "IN_1") (pintype "input"))
      (node (ref "J2") (pin "P$1") (pinfunction "1_P$1") (pintype "bidirectional"))
      (node (ref "R7") (pin "P$2") (pinfunction "P$2_P$2") (pintype "passive"))
    )
    (net (code "46") (name "unconnected-(IC1-BYP-Pad4)") (class "Default")
      (node (ref "IC1") (pin "4") (pinfunction "BYP_4") (pintype "passive"))
    )
    (net (code "47") (name "unconnected-(J3-Pad4)") (class "Default")
      (node (ref "J3") (pin "4") (pinfunction "4_4") (pintype "passive"))
    )
    (net (code "48") (name "unconnected-(J4-Pad1)") (class "Default")
      (node (ref "J4") (pin "1") (pinfunction "1_1") (pintype "bidirectional"))
    )
    (net (code "49") (name "unconnected-(U$1-RTS-Pad4)") (class "Default")
      (node (ref "U$1") (pin "4") (pinfunction "RTS_4") (pintype "bidirectional"))
    )
    (net (code "50") (name "unconnected-(U2-CLKOUT-Pad3)") (class "Default")
      (node (ref "U2") (pin "3") (pinfunction "CLKOUT_3") (pintype "bidirectional"))
    )
    (net (code "51") (name "unconnected-(U2-~{INT}-Pad13)") (class "Default")
      (node (ref "U2") (pin "13") (pinfunction "~{INT}_13") (pintype "bidirectional"))
    )
    (net (code "52") (name "unconnected-(U2-~{RX0BF}-Pad12)") (class "Default")
      (node (ref "U2") (pin "12") (pinfunction "~{RX0BF}_12") (pintype "bidirectional"))
    )
    (net (code "53") (name "unconnected-(U2-~{RX1BF}-Pad11)") (class "Default")
      (node (ref "U2") (pin "11") (pinfunction "~{RX1BF}_11") (pintype "bidirectional"))
    )
    (net (code "54") (name "unconnected-(U2-~{TX0RTS}-Pad4)") (class "Default")
      (node (ref "U2") (pin "4") (pinfunction "~{TX0RTS}_4") (pintype "bidirectional"))
    )
    (net (code "55") (name "unconnected-(U2-~{TX1RTS}-Pad5)") (class "Default")
      (node (ref "U2") (pin "5") (pinfunction "~{TX1RTS}_5") (pintype "bidirectional"))
    )
    (net (code "56") (name "unconnected-(U2-~{TX2RTS}-Pad7)") (class "Default")
      (node (ref "U2") (pin "7") (pinfunction "~{TX2RTS}_7") (pintype "bidirectional"))
    )
    (net (code "57") (name "unconnected-(U3-VREF-Pad5)") (class "Default")
      (node (ref "U3") (pin "5") (pinfunction "VREF_5") (pintype "output"))
    )
    (net (code "58") (name "unconnected-(U4-OSC_IN{slash}PC14-Pad2)") (class "Default")
      (node (ref "U4") (pin "2") (pinfunction "OSC_IN/PC14_2") (pintype "bidirectional"))
    )
    (net (code "59") (name "unconnected-(U4-OSC_OUT{slash}PC15-Pad3)") (class "Default")
      (node (ref "U4") (pin "3") (pinfunction "OSC_OUT/PC15_3") (pintype "bidirectional"))
    )
    (net (code "60") (name "unconnected-(U4-PA0-Pad6)") (class "Default")
      (node (ref "U4") (pin "6") (pinfunction "PA0_6") (pintype "bidirectional"))
    )
    (net (code "61") (name "unconnected-(U4-PA1-Pad7)") (class "Default")
      (node (ref "U4") (pin "7") (pinfunction "PA1_7") (pintype "bidirectional"))
    )
    (net (code "62") (name "unconnected-(U4-PA4-Pad10)") (class "Default")
      (node (ref "U4") (pin "10") (pinfunction "PA4_10") (pintype "bidirectional"))
    )
    (net (code "63") (name "unconnected-(U4-PA8-Pad18)") (class "Default")
      (node (ref "U4") (pin "18") (pinfunction "PA8_18") (pintype "bidirectional"))
    )
    (net (code "64") (name "unconnected-(U4-PA11-Pad21)") (class "Default")
      (node (ref "U4") (pin "21") (pinfunction "PA11_21") (pintype "bidirectional"))
    )
    (net (code "65") (name "unconnected-(U4-PA12-Pad22)") (class "Default")
      (node (ref "U4") (pin "22") (pinfunction "PA12_22") (pintype "bidirectional"))
    )
    (net (code "66") (name "unconnected-(U4-PA13-Pad23)") (class "Default")
      (node (ref "U4") (pin "23") (pinfunction "PA13_23") (pintype "bidirectional"))
    )
    (net (code "67") (name "unconnected-(U4-PA14-Pad24)") (class "Default")
      (node (ref "U4") (pin "24") (pinfunction "PA14_24") (pintype "bidirectional"))
    )
    (net (code "68") (name "unconnected-(U4-PA15-Pad25)") (class "Default")
      (node (ref "U4") (pin "25") (pinfunction "PA15_25") (pintype "bidirectional"))
    )
    (net (code "69") (name "unconnected-(U4-PB0-Pad14)") (class "Default")
      (node (ref "U4") (pin "14") (pinfunction "PB0_14") (pintype "bidirectional"))
    )
    (net (code "70") (name "unconnected-(U4-PB1-Pad15)") (class "Default")
      (node (ref "U4") (pin "15") (pinfunction "PB1_15") (pintype "bidirectional"))
    )
    (net (code "71") (name "unconnected-(U4-PB4-Pad27)") (class "Default")
      (node (ref "U4") (pin "27") (pinfunction "PB4_27") (pintype "bidirectional"))
    )
    (net (code "72") (name "unconnected-(U4-PB5-Pad28)") (class "Default")
      (node (ref "U4") (pin "28") (pinfunction "PB5_28") (pintype "bidirectional"))
    )
    (net (code "73") (name "unconnected-(U4-PB6-Pad29)") (class "Default")
      (node (ref "U4") (pin "29") (pinfunction "PB6_29") (pintype "bidirectional"))
    )
    (net (code "74") (name "unconnected-(U4-PB7-Pad30)") (class "Default")
      (node (ref "U4") (pin "30") (pinfunction "PB7_30") (pintype "bidirectional"))
    )
    (net (code "75") (name "unconnected-(U5-IO0-PadP$2)") (class "Default")
      (node (ref "U5") (pin "P$2") (pinfunction "IO0_P$2") (pintype "bidirectional"))
    )
    (net (code "76") (name "unconnected-(U5-IO6-PadP$8)") (class "Default")
      (node (ref "U5") (pin "P$8") (pinfunction "IO6_P$8") (pintype "bidirectional"))
    )
    (net (code "77") (name "unconnected-(U5-IO7-PadP$9)") (class "Default")
      (node (ref "U5") (pin "P$9") (pinfunction "IO7_P$9") (pintype "bidirectional"))
    )
    (net (code "78") (name "unconnected-(U5-IO10-PadP$13)") (class "Default")
      (node (ref "U5") (pin "P$13") (pinfunction "IO10_P$13") (pintype "bidirectional"))
    )
    (net (code "79") (name "unconnected-(U5-IO12-PadP$15)") (class "Default")
      (node (ref "U5") (pin "P$15") (pinfunction "IO12_P$15") (pintype "bidirectional"))
    )
    (net (code "80") (name "unconnected-(U5-IO14-PadP$17)") (class "Default")
      (node (ref "U5") (pin "P$17") (pinfunction "IO14_P$17") (pintype "bidirectional"))
    )
    (net (code "81") (name "unconnected-(U5-IO17-PadP$20)") (class "Default")
      (node (ref "U5") (pin "P$20") (pinfunction "IO17_P$20") (pintype "bidirectional"))
    )
  )
)
